# PrimalLogger_Feather.net
KiCad netlist of a schematic drawn in EAGLE
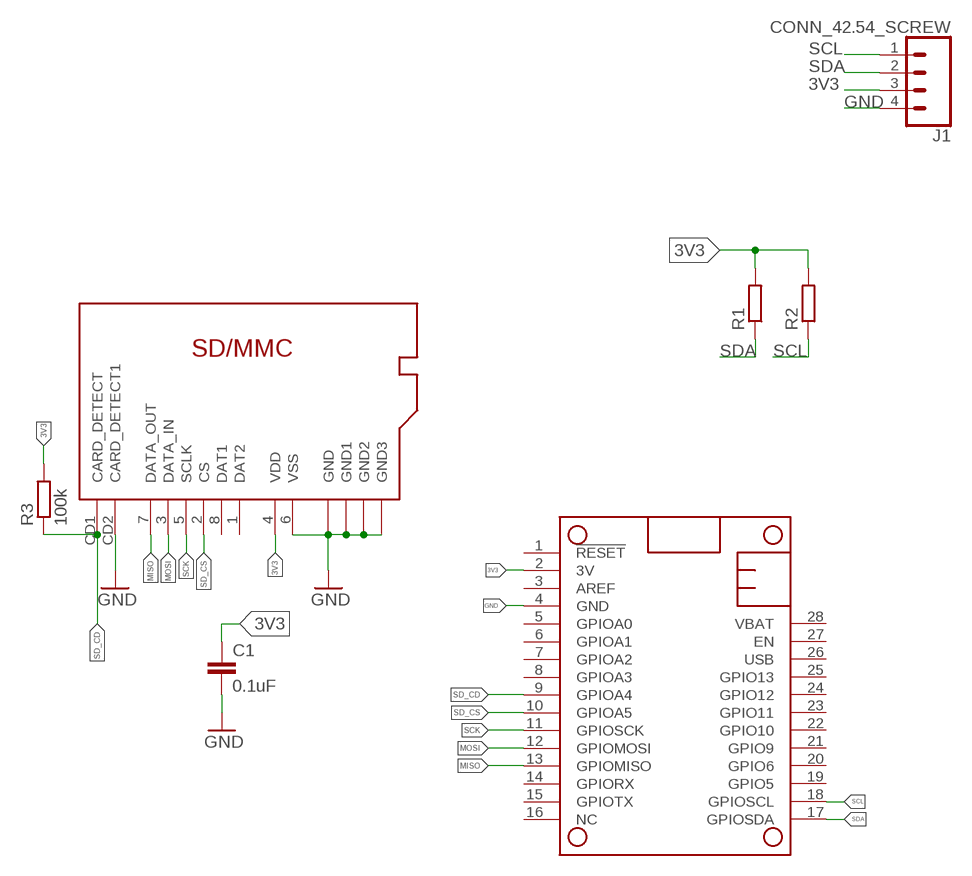
[diagram p0: schematic, sheet 1]

(export (version "E")
  (design (tool "Eeschema 10.0.6"))
  (components
    (comp (ref "C1")
      (value "0.1uF")
      (footprint "eagle-import:C0603")
      (fields (field (name "MF") "Murata") (field (name "MPN") "GCM188R71E104KA57D"))
      (libsource (lib "eagle-import") (part "C-EUC06030.1UF"))
    )
    (comp (ref "J1")
      (value "CONN_42.54_SCREW")
      (footprint "eagle-import:1X04_SCREW")
      (fields (field (name "MF") "On Shore") (field (name "MPN") "OSTVN04A150"))
      (libsource (lib "eagle-import") (part "CONN_42.54_SCREW"))
    )
    (comp (ref "MS1")
      (value "FEATHERWING_NODIM")
      (footprint "eagle-import:FEATHERWING_DIM")
      (libsource (lib "eagle-import") (part "FEATHERWING_NODIM"))
    )
    (comp (ref "R1")
      (value "R-EU_10KR0603")
      (footprint "eagle-import:R0603")
      (fields
        (field (name "MF") "Yageo")
        (field (name "MPN") "RC0603FR-0710KL")
        (field (name "VALUE_PART") "10k")
      )
      (libsource (lib "eagle-import") (part "R-EU_R060310K"))
    )
    (comp (ref "R2")
      (value "R-EU_10KR0603")
      (footprint "eagle-import:R0603")
      (fields
        (field (name "MF") "Yageo")
        (field (name "MPN") "RC0603FR-0710KL")
        (field (name "VALUE_PART") "10k")
      )
      (libsource (lib "eagle-import") (part "R-EU_R060310K"))
    )
    (comp (ref "R3")
      (value "100k")
      (footprint "eagle-import:R0603")
      (fields (field (name "MF") "Yageo") (field (name "MPN") "RC0603FR-07100KL"))
      (libsource (lib "eagle-import") (part "R-EU_R0603100K"))
    )
    (comp (ref "SD1")
      (value "MICRO_SD")
      (footprint "eagle-import:CUSTOM-PARTS_SD_MICRO")
      (libsource (lib "eagle-import") (part "MICRO_SD"))
    )
  )
  (nets
    (net (code "1") (name "/USB") (class "Default")
      (node (ref "MS1") (pin "26") (pinfunction "USB_26") (pintype "power_in"))
    )
    (net (code "2") (name "/VBAT") (class "Default")
      (node (ref "MS1") (pin "28") (pinfunction "VBAT_28") (pintype "power_in"))
    )
    (net (code "3") (name "3V3") (class "Default")
      (node (ref "C1") (pin "1") (pinfunction "1_1") (pintype "passive"))
      (node (ref "J1") (pin "3") (pinfunction "3_3") (pintype "passive"))
      (node (ref "MS1") (pin "2") (pinfunction "3V_2") (pintype "power_in"))
      (node (ref "R1") (pin "2") (pinfunction "2_2") (pintype "passive"))
      (node (ref "R2") (pin "2") (pinfunction "2_2") (pintype "passive"))
      (node (ref "R3") (pin "2") (pinfunction "2_2") (pintype "passive"))
      (node (ref "SD1") (pin "4") (pinfunction "VDD_4") (pintype "bidirectional"))
    )
    (net (code "4") (name "GND") (class "Default")
      (node (ref "C1") (pin "2") (pinfunction "2_2") (pintype "passive"))
      (node (ref "J1") (pin "4") (pinfunction "4_4") (pintype "passive"))
      (node (ref "MS1") (pin "4") (pinfunction "GND_4") (pintype "power_in"))
      (node (ref "SD1") (pin "6") (pinfunction "VSS_6") (pintype "bidirectional"))
      (node (ref "SD1") (pin "CD2") (pinfunction "CARD_DETECT1_CD2") (pintype "bidirectional"))
      (node (ref "SD1") (pin "GND@1") (pinfunction "GND_GND@1") (pintype "bidirectional"))
      (node (ref "SD1") (pin "GND@2") (pinfunction "GND1_GND@2") (pintype "bidirectional"))
      (node (ref "SD1") (pin "GND@3") (pinfunction "GND2_GND@3") (pintype "bidirectional"))
      (node (ref "SD1") (pin "GND@5") (pinfunction "GND3_GND@5") (pintype "bidirectional"))
    )
    (net (code "5") (name "MISO") (class "Default")
      (node (ref "MS1") (pin "13") (pinfunction "GPIOMISO_13") (pintype "bidirectional"))
      (node (ref "SD1") (pin "7") (pinfunction "DATA_OUT_7") (pintype "bidirectional"))
    )
    (net (code "6") (name "MOSI") (class "Default")
      (node (ref "MS1") (pin "12") (pinfunction "GPIOMOSI_12") (pintype "bidirectional"))
      (node (ref "SD1") (pin "3") (pinfunction "DATA_IN_3") (pintype "bidirectional"))
    )
    (net (code "7") (name "SCK") (class "Default")
      (node (ref "MS1") (pin "11") (pinfunction "GPIOSCK_11") (pintype "bidirectional"))
      (node (ref "SD1") (pin "5") (pinfunction "SCLK_5") (pintype "bidirectional"))
    )
    (net (code "8") (name "SCL") (class "Default")
      (node (ref "J1") (pin "1") (pinfunction "1_1") (pintype "passive"))
      (node (ref "MS1") (pin "18") (pinfunction "GPIOSCL_18") (pintype "bidirectional"))
      (node (ref "R2") (pin "1") (pinfunction "1_1") (pintype "passive"))
    )
    (net (code "9") (name "SDA") (class "Default")
      (node (ref "J1") (pin "2") (pinfunction "2_2") (pintype "passive"))
      (node (ref "MS1") (pin "17") (pinfunction "GPIOSDA_17") (pintype "bidirectional"))
      (node (ref "R1") (pin "1") (pinfunction "1_1") (pintype "passive"))
    )
    (net (code "10") (name "SD_CD") (class "Default")
      (node (ref "MS1") (pin "9") (pinfunction "GPIOA4_9") (pintype "bidirectional"))
      (node (ref "R3") (pin "1") (pinfunction "1_1") (pintype "passive"))
      (node (ref "SD1") (pin "CD1") (pinfunction "CARD_DETECT_CD1") (pintype "bidirectional"))
    )
    (net (code "11") (name "SD_CS") (class "Default")
      (node (ref "MS1") (pin "10") (pinfunction "GPIOA5_10") (pintype "bidirectional"))
      (node (ref "SD1") (pin "2") (pinfunction "CS_2") (pintype "bidirectional"))
    )
    (net (code "12") (name "unconnected-(MS1-AREF-Pad3)") (class "Default")
      (node (ref "MS1") (pin "3") (pinfunction "AREF_3") (pintype "passive"))
    )
    (net (code "13") (name "unconnected-(MS1-EN-Pad27)") (class "Default")
      (node (ref "MS1") (pin "27") (pinfunction "EN_27") (pintype "passive"))
    )
    (net (code "14") (name "unconnected-(MS1-GPIO5-Pad19)") (class "Default")
      (node (ref "MS1") (pin "19") (pinfunction "GPIO5_19") (pintype "bidirectional"))
    )
    (net (code "15") (name "unconnected-(MS1-GPIO6-Pad20)") (class "Default")
      (node (ref "MS1") (pin "20") (pinfunction "GPIO6_20") (pintype "bidirectional"))
    )
    (net (code "16") (name "unconnected-(MS1-GPIO9-Pad21)") (class "Default")
      (node (ref "MS1") (pin "21") (pinfunction "GPIO9_21") (pintype "bidirectional"))
    )
    (net (code "17") (name "unconnected-(MS1-GPIO10-Pad22)") (class "Default")
      (node (ref "MS1") (pin "22") (pinfunction "GPIO10_22") (pintype "bidirectional"))
    )
    (net (code "18") (name "unconnected-(MS1-GPIO11-Pad23)") (class "Default")
      (node (ref "MS1") (pin "23") (pinfunction "GPIO11_23") (pintype "bidirectional"))
    )
    (net (code "19") (name "unconnected-(MS1-GPIO12-Pad24)") (class "Default")
      (node (ref "MS1") (pin "24") (pinfunction "GPIO12_24") (pintype "bidirectional"))
    )
    (net (code "20") (name "unconnected-(MS1-GPIO13-Pad25)") (class "Default")
      (node (ref "MS1") (pin "25") (pinfunction "GPIO13_25") (pintype "bidirectional"))
    )
    (net (code "21") (name "unconnected-(MS1-GPIOA0-Pad5)") (class "Default")
      (node (ref "MS1") (pin "5") (pinfunction "GPIOA0_5") (pintype "bidirectional"))
    )
    (net (code "22") (name "unconnected-(MS1-GPIOA1-Pad6)") (class "Default")
      (node (ref "MS1") (pin "6") (pinfunction "GPIOA1_6") (pintype "bidirectional"))
    )
    (net (code "23") (name "unconnected-(MS1-GPIOA2-Pad7)") (class "Default")
      (node (ref "MS1") (pin "7") (pinfunction "GPIOA2_7") (pintype "bidirectional"))
    )
    (net (code "24") (name "unconnected-(MS1-GPIOA3-Pad8)") (class "Default")
      (node (ref "MS1") (pin "8") (pinfunction "GPIOA3_8") (pintype "bidirectional"))
    )
    (net (code "25") (name "unconnected-(MS1-GPIORX-Pad14)") (class "Default")
      (node (ref "MS1") (pin "14") (pinfunction "GPIORX_14") (pintype "bidirectional"))
    )
    (net (code "26") (name "unconnected-(MS1-GPIOTX-Pad15)") (class "Default")
      (node (ref "MS1") (pin "15") (pinfunction "GPIOTX_15") (pintype "bidirectional"))
    )
    (net (code "27") (name "unconnected-(MS1-NC-Pad16)") (class "Default")
      (node (ref "MS1") (pin "16") (pinfunction "NC_16") (pintype "passive"))
    )
    (net (code "28") (name "unconnected-(MS1-~{RESET}-Pad1)") (class "Default")
      (node (ref "MS1") (pin "1") (pinfunction "~{RESET}_1") (pintype "input"))
    )
    (net (code "29") (name "unconnected-(SD1-DAT1-Pad8)") (class "Default")
      (node (ref "SD1") (pin "8") (pinfunction "DAT1_8") (pintype "bidirectional"))
    )
    (net (code "30") (name "unconnected-(SD1-DAT2-Pad1)") (class "Default")
      (node (ref "SD1") (pin "1") (pinfunction "DAT2_1") (pintype "bidirectional"))
    )
  )
)
